# Safety_2019_V_3_0_TSAL.net
KiCad netlist of a schematic drawn in Altium Designer
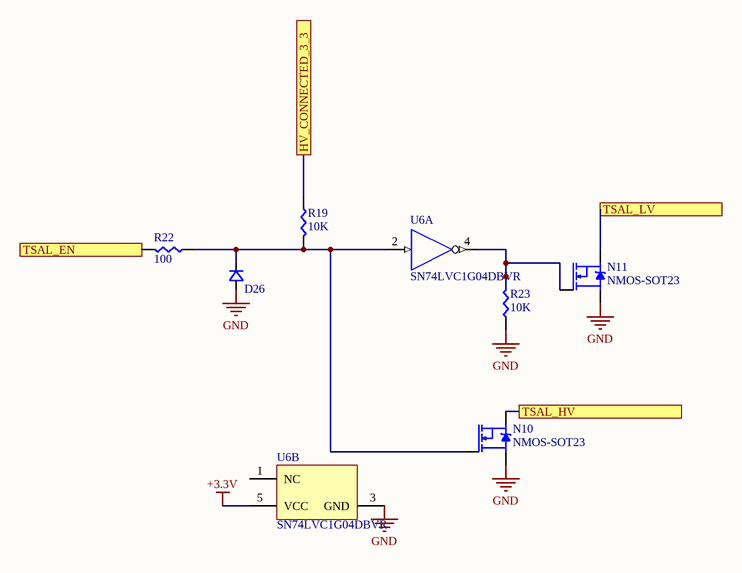
[diagram p0: Safety_2019_V_3_0_TSAL.SchDoc]

(export (version "E")
  (design (tool "Eeschema 10.0.6"))
  (components
    (comp (ref "D26")
      (value "12V ZENER")
      (footprint "SOD123")
      (libsource (lib "ife19_Elec_Library") (part "DIODE-SOD123"))
    )
    (comp (ref "N10")
      (value "NMOS-SOT23")
      (footprint "SOT23")
      (libsource (lib "ife19_Elec_Library") (part "NMOS-SOT23"))
    )
    (comp (ref "N11")
      (value "NMOS-SOT23")
      (footprint "SOT23")
      (libsource (lib "ife19_Elec_Library") (part "NMOS-SOT23"))
    )
    (comp (ref "R19")
      (value "10K")
      (footprint "RES-0603")
      (libsource (lib "ife19_Elec_Library") (part "RES-0603"))
    )
    (comp (ref "R22")
      (value "100")
      (footprint "RES-0603")
      (libsource (lib "ife19_Elec_Library") (part "RES-0603"))
    )
    (comp (ref "R23")
      (value "10K")
      (footprint "RES-0603")
      (libsource (lib "ife19_Elec_Library") (part "RES-0603"))
    )
    (comp (ref "U6")
      (value "SN74LVC1G04DBVR")
      (footprint "DBV0005A_L")
      (description "Single Inverter, DBV0005A, LARGE T&R")
      (fields
        (field (name "MANUFACTURER") "Texas Instruments")
        (field (name "GENERIC PART NUMBER") "SN74LVC1G04")
      )
      (libsource (lib "Altium Content Vault") (part "TI-SN74XXX1XX4-XX-5"))
    )
  )
  (nets
    (net (code "1") (name "+3.3V") (class "Default")
      (node (ref "U6") (pin "5") (pinfunction "VCC_5") (pintype "power_in"))
    )
    (net (code "2") (name "/HV_CONNECTED_3_3") (class "Default")
      (node (ref "R19") (pin "1") (pinfunction "1_1") (pintype "passive"))
    )
    (net (code "3") (name "/TSAL_EN") (class "Default")
      (node (ref "R22") (pin "2") (pinfunction "2_2") (pintype "passive"))
    )
    (net (code "4") (name "/TSAL_HV") (class "Default")
      (node (ref "N10") (pin "3") (pinfunction "D_3") (pintype "passive"))
    )
    (net (code "5") (name "/TSAL_LV") (class "Default")
      (node (ref "N11") (pin "3") (pinfunction "D_3") (pintype "passive"))
    )
    (net (code "6") (name "GND") (class "Default")
      (node (ref "D26") (pin "A") (pinfunction "A_A") (pintype "passive"))
      (node (ref "N10") (pin "2") (pinfunction "S_2") (pintype "passive"))
      (node (ref "N11") (pin "2") (pinfunction "S_2") (pintype "passive"))
      (node (ref "R23") (pin "1") (pinfunction "1_1") (pintype "passive"))
      (node (ref "U6") (pin "3") (pinfunction "GND_3") (pintype "power_in"))
    )
    (net (code "7") (name "Net-(N10-G)") (class "Default")
      (node (ref "D26") (pin "K") (pinfunction "K_K") (pintype "passive"))
      (node (ref "N10") (pin "1") (pinfunction "G_1") (pintype "passive"))
      (node (ref "R19") (pin "2") (pinfunction "2_2") (pintype "passive"))
      (node (ref "R22") (pin "1") (pinfunction "1_1") (pintype "passive"))
      (node (ref "U6") (pin "2") (pinfunction "A_2") (pintype "input"))
    )
    (net (code "8") (name "Net-(N11-G)") (class "Default")
      (node (ref "N11") (pin "1") (pinfunction "G_1") (pintype "passive"))
      (node (ref "R23") (pin "2") (pinfunction "2_2") (pintype "passive"))
      (node (ref "U6") (pin "4") (pinfunction "Y_4") (pintype "output"))
    )
    (net (code "9") (name "unconnected-(U6B-NC-Pad1)") (class "Default")
      (node (ref "U6") (pin "1") (pinfunction "NC_1") (pintype "passive"))
    )
  )
)
